# PROC099A_Pwr_RST_LEDs.net
KiCad netlist of a schematic drawn in Altium Designer
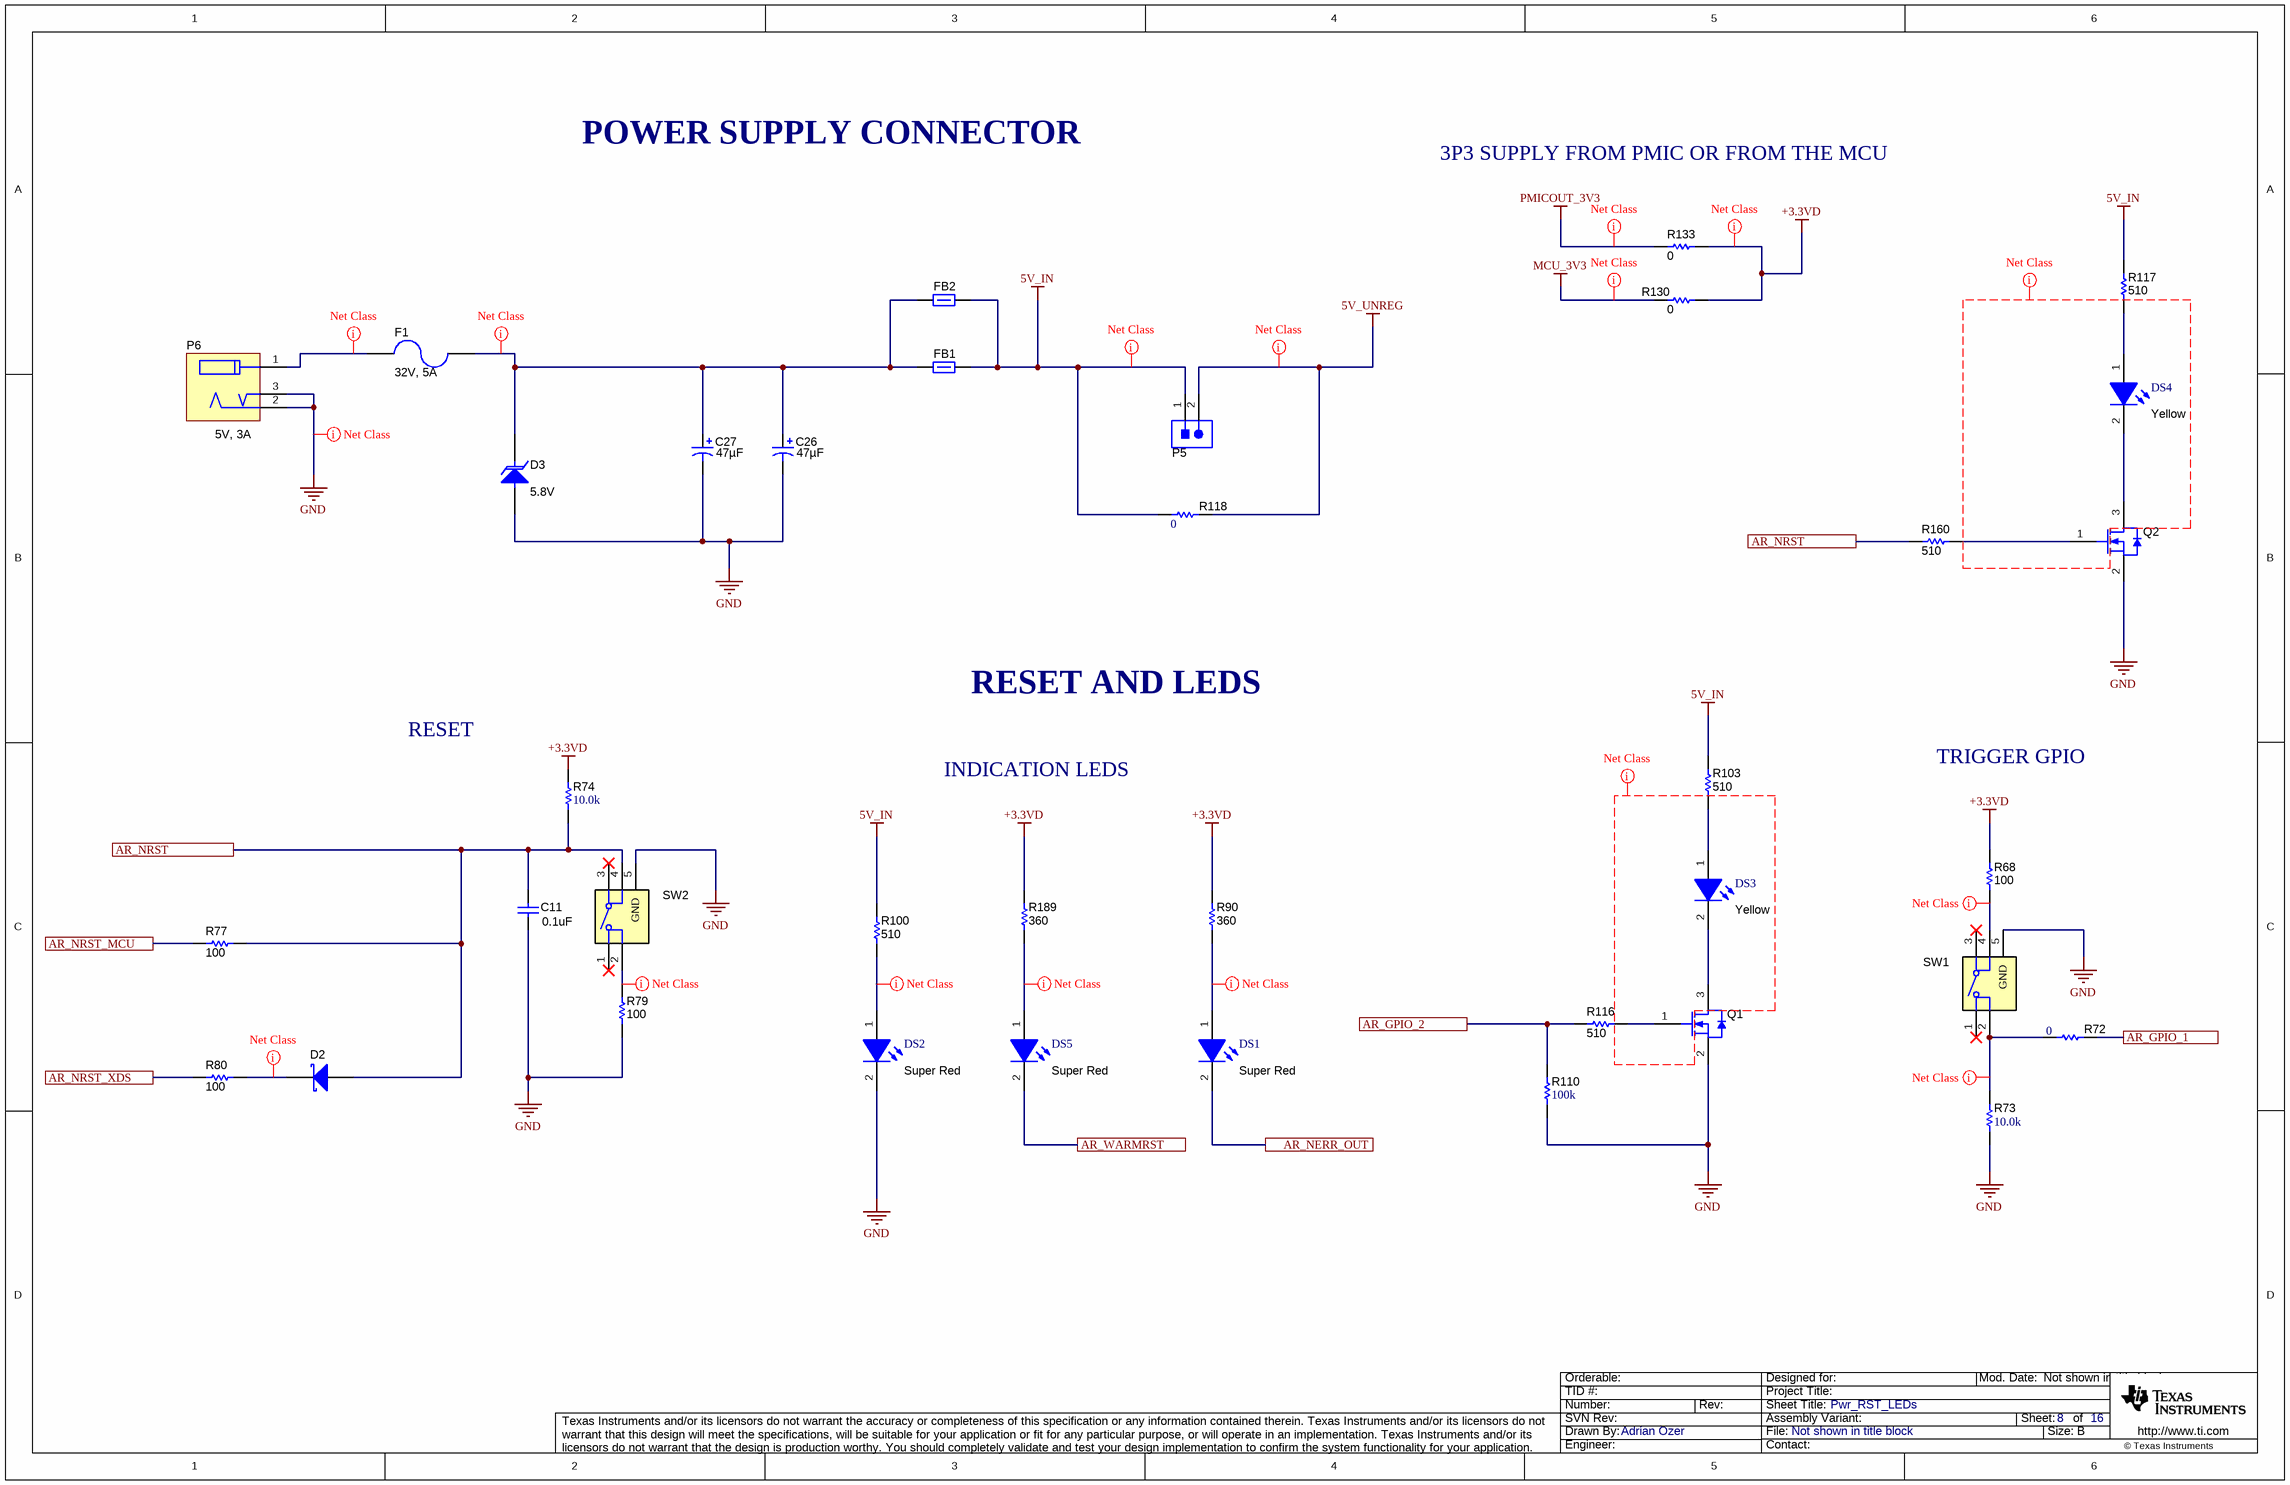
[diagram p0: PROC099A_Pwr_RST_LEDs.SchDoc]

(export (version "E")
  (design (tool "Eeschema 10.0.6"))
  (components
    (comp (ref "C11")
      (value "GCM155R71C104KA55D")
      (footprint "0402L")
      (description "CAP, CERM, 0.1 uF, 16 V, +/- 10%, X7R, 0402")
      (fields
        (field (name "MANUFACTURER") "MuRata")
        (field (name "VALUEDISPLAYED") "0.1uF")
        (field (name "PUBLISHER") "Texas Instruments")
      )
      (libsource (lib "Altium Vault - TI") (part "Capacitor"))
    )
    (comp (ref "C26")
      (value "T491B476K010AT")
      (footprint "3528-21")
      (description "CAP, TA, 47 µF, 10 V, +/- 10%, SMD")
      (fields (field (name "MANUFACTURER") "Kemet") (field (name "VALUEDISPLAYED") "47µF"))
      (libsource (lib "Altium Vault - TI") (part "Cap_Polarized"))
    )
    (comp (ref "C27")
      (value "T491B476K010AT")
      (footprint "3528-21")
      (description "CAP, TA, 47 µF, 10 V, +/- 10%, SMD")
      (fields (field (name "MANUFACTURER") "Kemet") (field (name "VALUEDISPLAYED") "47µF"))
      (libsource (lib "Altium Vault - TI") (part "Cap_Polarized"))
    )
    (comp (ref "D2")
      (value "SMS3923-040LF")
      (footprint "SOD-882")
      (description "Diode, Schottky,  V, 0.01 A, SOD-882")
      (fields (field (name "MANUFACTURER") "Skyworks Solutions"))
      (libsource (lib "Altium Vault - TI") (part "CMP-0078187-1"))
    )
    (comp (ref "D3")
      (value "5.8V")
      (footprint "SMB")
      (description "Diode, TVS, Uni, 5.8 V, 10.5 Vc, AEC-Q101, SMB")
      (fields (field (name "MANUFACTURER") "Littelfuse") (field (name "PARTNUMBER") "SZP6SMB6.8AT3G"))
      (libsource (lib "Altium Vault - TI") (part "Diode_TVS_Uni"))
    )
    (comp (ref "DS1")
      (value "Super Red")
      (footprint "SML-LX0603SRW_SuperRed")
      (description "LED, Super Red, SMD")
      (fields
        (field (name "MANUFACTURER") "Lumex")
        (field (name "PARTNUMBER") "SML-LX0603SRW-TR")
        (field (name "PUBLISHER") "Texas Instruments")
      )
      (libsource (lib "Altium Vault - TI") (part "CMP-0002876-1"))
    )
    (comp (ref "DS2")
      (value "Super Red")
      (footprint "SML-LX0603SRW_SuperRed")
      (description "LED, Super Red, SMD")
      (fields
        (field (name "MANUFACTURER") "Lumex")
        (field (name "PARTNUMBER") "SML-LX0603SRW-TR")
        (field (name "PUBLISHER") "Texas Instruments")
      )
      (libsource (lib "Altium Vault - TI") (part "CMP-0002876-1"))
    )
    (comp (ref "DS3")
      (value "Yellow")
      (footprint "SML-E1_Yellow")
      (description "LED, Yellow, SMD")
      (fields
        (field (name "MANUFACTURER") "Rohm")
        (field (name "PARTNUMBER") "SML-E12Y8WT86")
        (field (name "PUBLISHER") "Texas Instruments")
      )
      (libsource (lib "Altium Vault - TI") (part "LED"))
    )
    (comp (ref "DS4")
      (value "Yellow")
      (footprint "SML-E1_Yellow")
      (description "LED, Yellow, SMD")
      (fields
        (field (name "MANUFACTURER") "Rohm")
        (field (name "PARTNUMBER") "SML-E12Y8WT86")
        (field (name "PUBLISHER") "Texas Instruments")
      )
      (libsource (lib "Altium Vault - TI") (part "CMP-0002977-2"))
    )
    (comp (ref "DS5")
      (value "Super Red")
      (footprint "SML-LX0603SRW_SuperRed")
      (description "LED, Super Red, SMD")
      (fields
        (field (name "MANUFACTURER") "Lumex")
        (field (name "PARTNUMBER") "SML-LX0603SRW-TR")
        (field (name "PUBLISHER") "Texas Instruments")
      )
      (libsource (lib "Altium Vault - TI") (part "CMP-0002876-1"))
    )
    (comp (ref "F1")
      (value "32V, 5A")
      (footprint "1206")
      (description "Fuse, 5 A, 32VAC/VDC, SMD")
      (fields (field (name "MANUFACTURER") "Littelfuse") (field (name "PARTNUMBER") "0440005.WR"))
      (libsource (lib "Altium Vault - TI") (part "Fuse"))
    )
    (comp (ref "FB1")
      (value "BLM21PG300SH1D")
      (footprint "0805_HV")
      (description "Ferrite Bead, 30 ohm @ 100 MHz, 4 A, 0805")
      (fields (field (name "MANUFACTURER") "MuRata") (field (name "PUBLISHER") "Texas Instruments"))
      (libsource (lib "Altium Vault - TI") (part "CMP-0003364-1"))
    )
    (comp (ref "FB2")
      (value "BLM21PG300SH1D")
      (footprint "0805_HV")
      (description "Ferrite Bead, 30 ohm @ 100 MHz, 4 A, 0805")
      (fields (field (name "MANUFACTURER") "MuRata") (field (name "PUBLISHER") "Texas Instruments"))
      (libsource (lib "Altium Vault - TI") (part "CMP-0003364-1"))
    )
    (comp (ref "P5")
      (value "TSW-102-07-G-S")
      (footprint "TSW-102-07-G-S")
      (description "Header, 100mil, 2x1, Gold, TH")
      (fields (field (name "MANUFACTURER") "Samtec"))
      (libsource (lib "Altium Vault - TI") (part "Header_2x1"))
    )
    (comp (ref "P6")
      (value "PJ-002AH")
      (footprint "CUI_PJ-002AH")
      (description "DC POWER JACK, R/A, TH")
      (fields (field (name "MANUFACTURER") "CUI Inc."))
      (libsource (lib "Altium Vault - TI") (part "CONN_DC JACK"))
    )
    (comp (ref "Q1")
      (value "BSS123")
      (footprint "SOT-23")
      (description "MOSFET, N-CH, 100 V, 0.17 A, SOT-23")
      (fields
        (field (name "MANUFACTURER") "Fairchild Semiconductor")
        (field (name "PUBLISHER") "Texas Instruments")
      )
      (libsource (lib "Altium Vault - TI") (part "MOSFET_N_D3G1S2"))
    )
    (comp (ref "Q2")
      (value "BSS123")
      (footprint "SOT-23")
      (description "MOSFET, N-CH, 100 V, 0.17 A, SOT-23")
      (fields
        (field (name "MANUFACTURER") "Fairchild Semiconductor")
        (field (name "PUBLISHER") "Texas Instruments")
      )
      (libsource (lib "Altium Vault - TI") (part "MOSFET_N_D3G1S2"))
    )
    (comp (ref "R68")
      (value "ERJ-2GEJ101X")
      (footprint "0402L")
      (description "RES, 100, 5%, 0.1 W, AEC-Q200 Grade 0, 0402")
      (fields
        (field (name "MANUFACTURER") "Panasonic")
        (field (name "VALUEDISPLAYED") "100")
        (field (name "PUBLISHER") "Texas Instruments")
      )
      (libsource (lib "Altium Vault - TI") (part "Resistor"))
    )
    (comp (ref "R72")
      (value "CRCW02010000Z0ED")
      (footprint "0201_Silk")
      (description "RES, 0, 5%, 0.05 W, 0201")
      (fields (field (name "MANUFACTURER") "Vishay-Dale") (field (name "VALUEDISPLAYED") "0"))
      (libsource (lib "Altium Vault - TI") (part "Resistor"))
    )
    (comp (ref "R73")
      (value "CRCW040210K0FKED")
      (footprint "0402L")
      (description "RES, 10.0 k, 1%, 0.063 W, AEC-Q200 Grade 0, 0402")
      (fields (field (name "MANUFACTURER") "Vishay-Dale") (field (name "VALUEDISPLAYED") "10.0k"))
      (libsource (lib "Altium Vault - TI") (part "Resistor"))
    )
    (comp (ref "R74")
      (value "CRCW040210K0FKED")
      (footprint "0402L")
      (description "RES, 10.0 k, 1%, 0.063 W, AEC-Q200 Grade 0, 0402")
      (fields (field (name "MANUFACTURER") "Vishay-Dale") (field (name "VALUEDISPLAYED") "10.0k"))
      (libsource (lib "Altium Vault - TI") (part "Resistor"))
    )
    (comp (ref "R77")
      (value "ERJ-2GEJ101X")
      (footprint "0402L")
      (description "RES, 100, 5%, 0.1 W, AEC-Q200 Grade 0, 0402")
      (fields
        (field (name "MANUFACTURER") "Panasonic")
        (field (name "VALUEDISPLAYED") "100")
        (field (name "PUBLISHER") "Texas Instruments")
      )
      (libsource (lib "Altium Vault - TI") (part "Resistor"))
    )
    (comp (ref "R79")
      (value "ERJ-2GEJ101X")
      (footprint "0402L")
      (description "RES, 100, 5%, 0.1 W, AEC-Q200 Grade 0, 0402")
      (fields
        (field (name "MANUFACTURER") "Panasonic")
        (field (name "VALUEDISPLAYED") "100")
        (field (name "PUBLISHER") "Texas Instruments")
      )
      (libsource (lib "Altium Vault - TI") (part "Resistor"))
    )
    (comp (ref "R80")
      (value "ERJ-2GEJ101X")
      (footprint "0402L")
      (description "RES, 100, 5%, 0.1 W, AEC-Q200 Grade 0, 0402")
      (fields
        (field (name "MANUFACTURER") "Panasonic")
        (field (name "VALUEDISPLAYED") "100")
        (field (name "PUBLISHER") "Texas Instruments")
      )
      (libsource (lib "Altium Vault - TI") (part "Resistor"))
    )
    (comp (ref "R90")
      (value "ERJ-2GEJ361X")
      (footprint "0402L")
      (description "RES, 360, 5%, 0.1 W, AEC-Q200 Grade 0, 0402")
      (fields (field (name "MANUFACTURER") "Panasonic") (field (name "VALUEDISPLAYED") "360"))
      (libsource (lib "Altium Vault - TI") (part "Resistor"))
    )
    (comp (ref "R100")
      (value "ERJ-2GEJ511X")
      (footprint "0402L")
      (description "RES, 510, 5%, 0.1 W, AEC-Q200 Grade 0, 0402")
      (fields (field (name "MANUFACTURER") "Panasonic") (field (name "VALUEDISPLAYED") "510"))
      (libsource (lib "Altium Vault - TI") (part "Resistor"))
    )
    (comp (ref "R103")
      (value "ERJ-2GEJ511X")
      (footprint "0402L")
      (description "RES, 510, 5%, 0.1 W, AEC-Q200 Grade 0, 0402")
      (fields (field (name "MANUFACTURER") "Panasonic") (field (name "VALUEDISPLAYED") "510"))
      (libsource (lib "Altium Vault - TI") (part "Resistor"))
    )
    (comp (ref "R110")
      (value "CRCW0402100KFKED")
      (footprint "0402L")
      (description "RES, 100 k, 1%, 0.063 W, AEC-Q200 Grade 0, 0402")
      (fields (field (name "MANUFACTURER") "Vishay-Dale") (field (name "VALUEDISPLAYED") "100k"))
      (libsource (lib "Altium Vault - TI") (part "Resistor"))
    )
    (comp (ref "R116")
      (value "ERJ-2GEJ511X")
      (footprint "0402L")
      (description "RES, 510, 5%, 0.1 W, AEC-Q200 Grade 0, 0402")
      (fields (field (name "MANUFACTURER") "Panasonic") (field (name "VALUEDISPLAYED") "510"))
      (libsource (lib "Altium Vault - TI") (part "Resistor"))
    )
    (comp (ref "R117")
      (value "ERJ-2GEJ511X")
      (footprint "0402L")
      (description "RES, 510, 5%, 0.1 W, AEC-Q200 Grade 0, 0402")
      (fields (field (name "MANUFACTURER") "Panasonic") (field (name "VALUEDISPLAYED") "510"))
      (libsource (lib "Altium Vault - TI") (part "Resistor"))
    )
    (comp (ref "R118")
      (value "CRCW20100000Z0EF")
      (footprint "2010")
      (description "RES, 0, 5%, 0.75 W, AEC-Q200 Grade 0, 2010")
      (fields (field (name "MANUFACTURER") "Vishay-Dale") (field (name "VALUEDISPLAYED") "0"))
      (libsource (lib "Altium Vault - TI") (part "Resistor"))
    )
    (comp (ref "R130")
      (value "MCT06030Z0000ZP500")
      (footprint "0603")
      (description "RES, 0, 5%, 0.125 W, 0603")
      (fields
        (field (name "MANUFACTURER") "Vishay/Beyschlag")
        (field (name "VALUEDISPLAYED") "0")
        (field (name "PUBLISHER") "Texas Instruments")
      )
      (libsource (lib "Altium Vault - TI") (part "CMP-0025884-3"))
    )
    (comp (ref "R133")
      (value "MCT06030Z0000ZP500")
      (footprint "0603")
      (description "RES, 0, 5%, 0.125 W, 0603")
      (fields
        (field (name "MANUFACTURER") "Vishay/Beyschlag")
        (field (name "VALUEDISPLAYED") "0")
        (field (name "PUBLISHER") "Texas Instruments")
      )
      (libsource (lib "Altium Vault - TI") (part "Resistor"))
    )
    (comp (ref "R160")
      (value "ERJ-2GEJ511X")
      (footprint "0402L")
      (description "RES, 510, 5%, 0.1 W, AEC-Q200 Grade 0, 0402")
      (fields (field (name "MANUFACTURER") "Panasonic") (field (name "VALUEDISPLAYED") "510"))
      (libsource (lib "Altium Vault - TI") (part "Resistor"))
    )
    (comp (ref "R189")
      (value "ERJ-2GEJ361X")
      (footprint "0402L")
      (description "RES, 360, 5%, 0.1 W, AEC-Q200 Grade 0, 0402")
      (fields (field (name "MANUFACTURER") "Panasonic") (field (name "VALUEDISPLAYED") "360"))
      (libsource (lib "Altium Vault - TI") (part "Resistor"))
    )
    (comp (ref "SW1")
      (value "KMR243GLFG")
      (footprint "SW_KMR243GLFG")
      (description "Switch, SPST-NO, Off-Mom, 0.01 A, 32 VDC, SMD")
      (fields (field (name "MANUFACTURER") "C&K Components") (field (name "PUBLISHER") "Texas Instruments"))
      (libsource (lib "Altium Vault - TI") (part "CMP-0002325-1"))
    )
    (comp (ref "SW2")
      (value "KMR243GLFG")
      (footprint "SW_KMR243GLFG")
      (description "Switch, SPST-NO, Off-Mom, 0.01 A, 32 VDC, SMD")
      (fields (field (name "MANUFACTURER") "C&K Components") (field (name "PUBLISHER") "Texas Instruments"))
      (libsource (lib "Altium Vault - TI") (part "CMP-0002325-1"))
    )
  )
  (nets
    (net (code "1") (name "+3.3VD") (class "Default")
      (node (ref "R130") (pin "2") (pinfunction "2_2") (pintype "passive"))
      (node (ref "R133") (pin "2") (pinfunction "2_2") (pintype "passive"))
      (node (ref "R189") (pin "2") (pinfunction "2_2") (pintype "passive"))
      (node (ref "R68") (pin "2") (pinfunction "2_2") (pintype "passive"))
      (node (ref "R74") (pin "2") (pinfunction "2_2") (pintype "passive"))
      (node (ref "R90") (pin "2") (pinfunction "2_2") (pintype "passive"))
    )
    (net (code "2") (name "/AR_GPIO_1") (class "Default")
      (node (ref "R72") (pin "2") (pinfunction "2_2") (pintype "passive"))
    )
    (net (code "3") (name "/AR_GPIO_2") (class "Default")
      (node (ref "R110") (pin "2") (pinfunction "2_2") (pintype "passive"))
      (node (ref "R116") (pin "1") (pinfunction "1_1") (pintype "passive"))
    )
    (net (code "4") (name "/AR_NERR_OUT") (class "Default")
      (node (ref "DS1") (pin "2") (pinfunction "K_2") (pintype "passive"))
    )
    (net (code "5") (name "/AR_NRST") (class "Default")
      (node (ref "C11") (pin "2") (pinfunction "2_2") (pintype "passive"))
      (node (ref "D2") (pin "2") (pinfunction "A_2") (pintype "passive"))
      (node (ref "R160") (pin "1") (pinfunction "1_1") (pintype "passive"))
      (node (ref "R74") (pin "1") (pinfunction "1_1") (pintype "passive"))
      (node (ref "R77") (pin "2") (pinfunction "2_2") (pintype "passive"))
      (node (ref "SW2") (pin "4") (pinfunction "4_4") (pintype "passive"))
    )
    (net (code "6") (name "/AR_NRST_MCU") (class "Default")
      (node (ref "R77") (pin "1") (pinfunction "1_1") (pintype "passive"))
    )
    (net (code "7") (name "/AR_NRST_XDS") (class "Default")
      (node (ref "R80") (pin "1") (pinfunction "1_1") (pintype "passive"))
    )
    (net (code "8") (name "/AR_WARMRST") (class "Default")
      (node (ref "DS5") (pin "2") (pinfunction "K_2") (pintype "passive"))
    )
    (net (code "9") (name "5V_IN") (class "Default")
      (node (ref "FB1") (pin "2") (pinfunction "2_2") (pintype "passive"))
      (node (ref "FB2") (pin "2") (pinfunction "2_2") (pintype "passive"))
      (node (ref "P5") (pin "1") (pinfunction "1_1") (pintype "passive"))
      (node (ref "R100") (pin "2") (pinfunction "2_2") (pintype "passive"))
      (node (ref "R103") (pin "2") (pinfunction "2_2") (pintype "passive"))
      (node (ref "R117") (pin "2") (pinfunction "2_2") (pintype "passive"))
      (node (ref "R118") (pin "1") (pinfunction "1_1") (pintype "passive"))
    )
    (net (code "10") (name "5V_UNREG") (class "Default")
      (node (ref "P5") (pin "2") (pinfunction "2_2") (pintype "passive"))
      (node (ref "R118") (pin "2") (pinfunction "2_2") (pintype "passive"))
    )
    (net (code "11") (name "GND") (class "Default")
      (node (ref "C11") (pin "1") (pinfunction "1_1") (pintype "passive"))
      (node (ref "C26") (pin "2") (pinfunction "-_2") (pintype "passive"))
      (node (ref "C27") (pin "2") (pinfunction "-_2") (pintype "passive"))
      (node (ref "D3") (pin "2") (pinfunction "A_2") (pintype "passive"))
      (node (ref "DS2") (pin "2") (pinfunction "K_2") (pintype "passive"))
      (node (ref "P6") (pin "2") (pinfunction "2_2") (pintype "passive"))
      (node (ref "P6") (pin "3") (pinfunction "3_3") (pintype "passive"))
      (node (ref "Q1") (pin "2") (pinfunction "S_2") (pintype "passive"))
      (node (ref "Q2") (pin "2") (pinfunction "S_2") (pintype "passive"))
      (node (ref "R110") (pin "1") (pinfunction "1_1") (pintype "passive"))
      (node (ref "R73") (pin "1") (pinfunction "1_1") (pintype "passive"))
      (node (ref "R79") (pin "1") (pinfunction "1_1") (pintype "passive"))
      (node (ref "SW1") (pin "5") (pinfunction "GND_5") (pintype "passive"))
      (node (ref "SW2") (pin "5") (pinfunction "GND_5") (pintype "passive"))
    )
    (net (code "12") (name "MCU_3V3") (class "Default")
      (node (ref "R130") (pin "1") (pinfunction "1_1") (pintype "passive"))
    )
    (net (code "13") (name "Net-(C26-+)") (class "Default")
      (node (ref "C26") (pin "1") (pinfunction "+_1") (pintype "passive"))
      (node (ref "C27") (pin "1") (pinfunction "+_1") (pintype "passive"))
      (node (ref "D3") (pin "1") (pinfunction "K_1") (pintype "passive"))
      (node (ref "F1") (pin "1") (pinfunction "1_1") (pintype "passive"))
      (node (ref "FB1") (pin "1") (pinfunction "1_1") (pintype "passive"))
      (node (ref "FB2") (pin "1") (pinfunction "1_1") (pintype "passive"))
    )
    (net (code "14") (name "Net-(D2-K)") (class "Default")
      (node (ref "D2") (pin "1") (pinfunction "K_1") (pintype "passive"))
      (node (ref "R80") (pin "2") (pinfunction "2_2") (pintype "passive"))
    )
    (net (code "15") (name "Net-(DS1-A)") (class "Default")
      (node (ref "DS1") (pin "1") (pinfunction "A_1") (pintype "passive"))
      (node (ref "R90") (pin "1") (pinfunction "1_1") (pintype "passive"))
    )
    (net (code "16") (name "Net-(DS2-A)") (class "Default")
      (node (ref "DS2") (pin "1") (pinfunction "A_1") (pintype "passive"))
      (node (ref "R100") (pin "1") (pinfunction "1_1") (pintype "passive"))
    )
    (net (code "17") (name "Net-(DS3-A)") (class "Default")
      (node (ref "DS3") (pin "1") (pinfunction "A_1") (pintype "passive"))
      (node (ref "R103") (pin "1") (pinfunction "1_1") (pintype "passive"))
    )
    (net (code "18") (name "Net-(DS3-K)") (class "Default")
      (node (ref "DS3") (pin "2") (pinfunction "K_2") (pintype "passive"))
      (node (ref "Q1") (pin "3") (pinfunction "D_3") (pintype "passive"))
    )
    (net (code "19") (name "Net-(DS4-A)") (class "Default")
      (node (ref "DS4") (pin "1") (pinfunction "A_1") (pintype "passive"))
      (node (ref "R117") (pin "1") (pinfunction "1_1") (pintype "passive"))
    )
    (net (code "20") (name "Net-(DS4-K)") (class "Default")
      (node (ref "DS4") (pin "2") (pinfunction "K_2") (pintype "passive"))
      (node (ref "Q2") (pin "3") (pinfunction "D_3") (pintype "passive"))
    )
    (net (code "21") (name "Net-(DS5-A)") (class "Default")
      (node (ref "DS5") (pin "1") (pinfunction "A_1") (pintype "passive"))
      (node (ref "R189") (pin "1") (pinfunction "1_1") (pintype "passive"))
    )
    (net (code "22") (name "Net-(F1-Pad2)") (class "Default")
      (node (ref "F1") (pin "2") (pinfunction "2_2") (pintype "passive"))
      (node (ref "P6") (pin "1") (pinfunction "1_1") (pintype "passive"))
    )
    (net (code "23") (name "Net-(Q1-G)") (class "Default")
      (node (ref "Q1") (pin "1") (pinfunction "G_1") (pintype "passive"))
      (node (ref "R116") (pin "2") (pinfunction "2_2") (pintype "passive"))
    )
    (net (code "24") (name "Net-(Q2-G)") (class "Default")
      (node (ref "Q2") (pin "1") (pinfunction "G_1") (pintype "passive"))
      (node (ref "R160") (pin "2") (pinfunction "2_2") (pintype "passive"))
    )
    (net (code "25") (name "Net-(R68-Pad1)") (class "Default")
      (node (ref "R68") (pin "1") (pinfunction "1_1") (pintype "passive"))
      (node (ref "SW1") (pin "4") (pinfunction "4_4") (pintype "passive"))
    )
    (net (code "26") (name "Net-(R72-Pad1)") (class "Default")
      (node (ref "R72") (pin "1") (pinfunction "1_1") (pintype "passive"))
      (node (ref "R73") (pin "2") (pinfunction "2_2") (pintype "passive"))
      (node (ref "SW1") (pin "2") (pinfunction "2_2") (pintype "passive"))
    )
    (net (code "27") (name "Net-(R79-Pad2)") (class "Default")
      (node (ref "R79") (pin "2") (pinfunction "2_2") (pintype "passive"))
      (node (ref "SW2") (pin "2") (pinfunction "2_2") (pintype "passive"))
    )
    (net (code "28") (name "PMICOUT_3V3") (class "Default")
      (node (ref "R133") (pin "1") (pinfunction "1_1") (pintype "passive"))
    )
    (net (code "29") (name "unconnected-(SW1-Pad1)") (class "Default")
      (node (ref "SW1") (pin "1") (pinfunction "1_1") (pintype "passive+no_connect"))
    )
    (net (code "30") (name "unconnected-(SW1-Pad3)") (class "Default")
      (node (ref "SW1") (pin "3") (pinfunction "3_3") (pintype "passive+no_connect"))
    )
    (net (code "31") (name "unconnected-(SW2-Pad1)") (class "Default")
      (node (ref "SW2") (pin "1") (pinfunction "1_1") (pintype "passive+no_connect"))
    )
    (net (code "32") (name "unconnected-(SW2-Pad3)") (class "Default")
      (node (ref "SW2") (pin "3") (pinfunction "3_3") (pintype "passive+no_connect"))
    )
  )
)
